# PCB_Keyboard_mark-2.net
KiCad netlist of a schematic drawn in EasyEDA
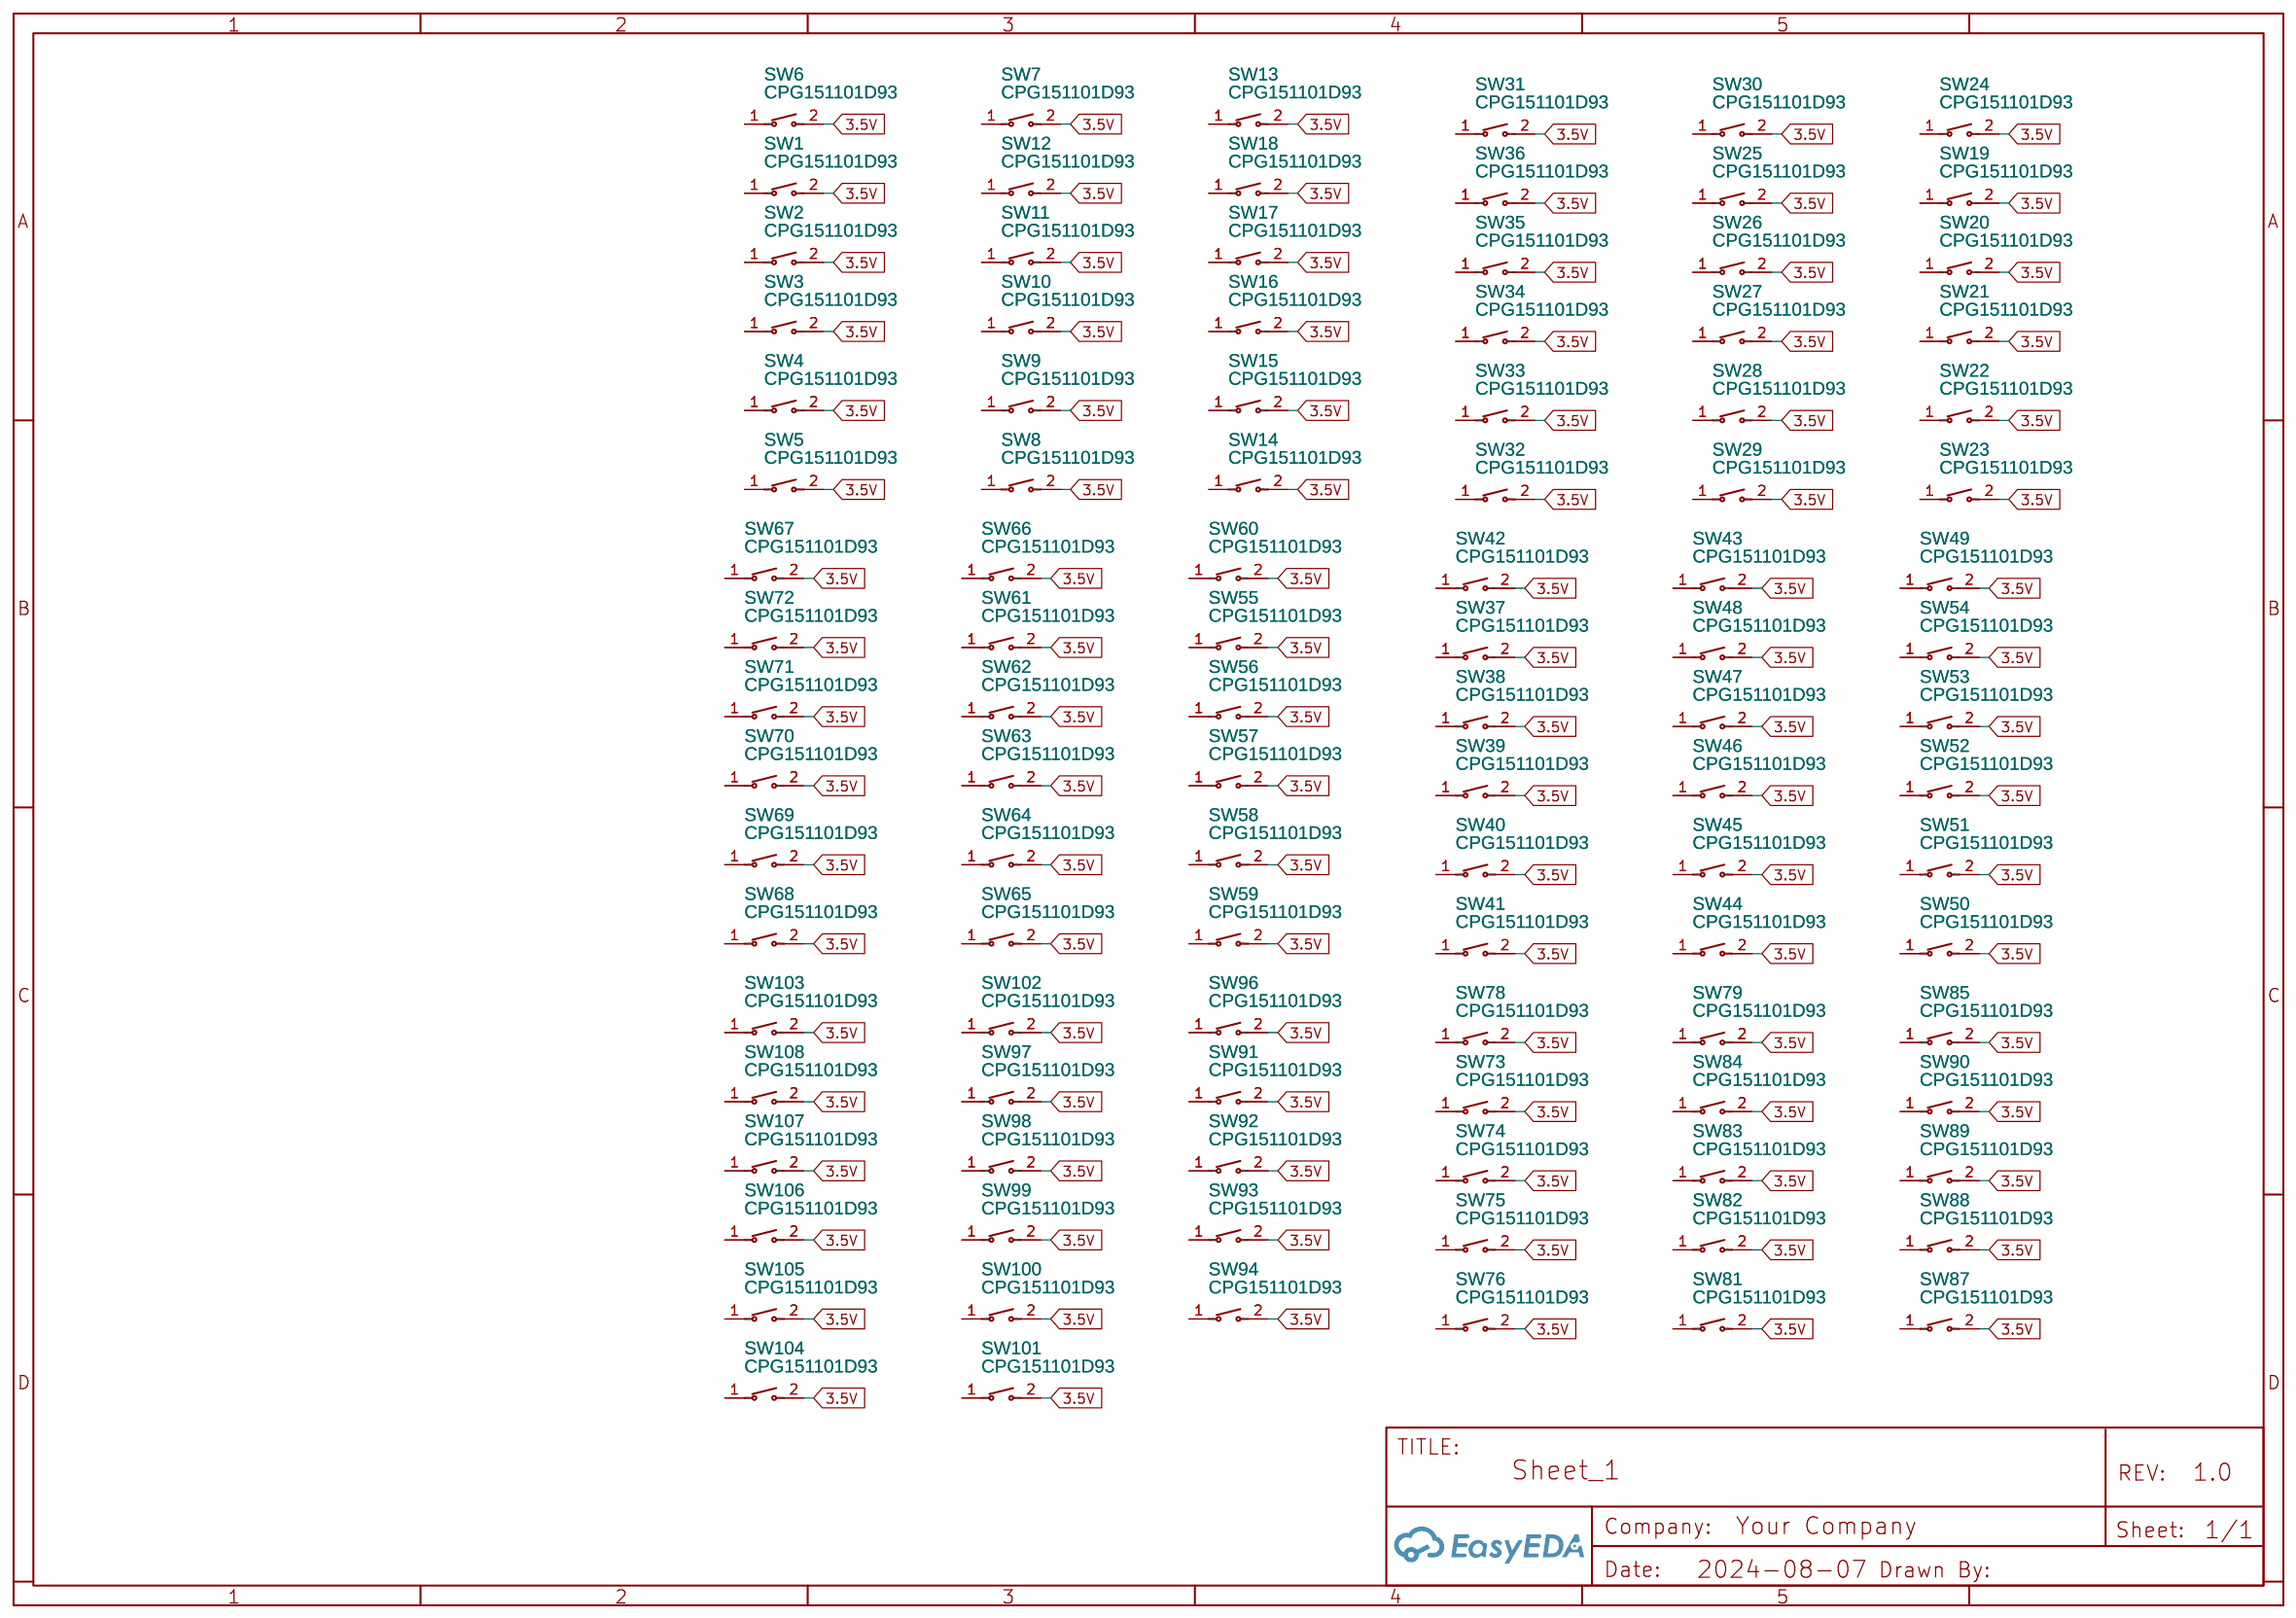
[diagram p0: schematic sheet]

(export (version "E")
  (design (tool "Eeschema 10.0.6"))
  (components
    (comp (ref "SW1")
      (value "CPG151101D93")
      (fields (field (name "Manufacturer") "Kailh(凯华)"))
      (libsource (lib "") (part "CPG151101D93"))
    )
    (comp (ref "SW2")
      (value "CPG151101D93")
      (fields (field (name "Manufacturer") "Kailh(凯华)"))
      (libsource (lib "") (part "CPG151101D93"))
    )
    (comp (ref "SW3")
      (value "CPG151101D93")
      (fields (field (name "Manufacturer") "Kailh(凯华)"))
      (libsource (lib "") (part "CPG151101D93"))
    )
    (comp (ref "SW4")
      (value "CPG151101D93")
      (fields (field (name "Manufacturer") "Kailh(凯华)"))
      (libsource (lib "") (part "CPG151101D93"))
    )
    (comp (ref "SW5")
      (value "CPG151101D93")
      (fields (field (name "Manufacturer") "Kailh(凯华)"))
      (libsource (lib "") (part "CPG151101D93"))
    )
    (comp (ref "SW6")
      (value "CPG151101D93")
      (fields (field (name "Manufacturer") "Kailh(凯华)"))
      (libsource (lib "") (part "CPG151101D93"))
    )
    (comp (ref "SW7")
      (value "CPG151101D93")
      (fields (field (name "Manufacturer") "Kailh(凯华)"))
      (libsource (lib "") (part "CPG151101D93"))
    )
    (comp (ref "SW8")
      (value "CPG151101D93")
      (fields (field (name "Manufacturer") "Kailh(凯华)"))
      (libsource (lib "") (part "CPG151101D93"))
    )
    (comp (ref "SW9")
      (value "CPG151101D93")
      (fields (field (name "Manufacturer") "Kailh(凯华)"))
      (libsource (lib "") (part "CPG151101D93"))
    )
    (comp (ref "SW10")
      (value "CPG151101D93")
      (fields (field (name "Manufacturer") "Kailh(凯华)"))
      (libsource (lib "") (part "CPG151101D93"))
    )
    (comp (ref "SW11")
      (value "CPG151101D93")
      (fields (field (name "Manufacturer") "Kailh(凯华)"))
      (libsource (lib "") (part "CPG151101D93"))
    )
    (comp (ref "SW12")
      (value "CPG151101D93")
      (fields (field (name "Manufacturer") "Kailh(凯华)"))
      (libsource (lib "") (part "CPG151101D93"))
    )
    (comp (ref "SW13")
      (value "CPG151101D93")
      (fields (field (name "Manufacturer") "Kailh(凯华)"))
      (libsource (lib "") (part "CPG151101D93"))
    )
    (comp (ref "SW14")
      (value "CPG151101D93")
      (fields (field (name "Manufacturer") "Kailh(凯华)"))
      (libsource (lib "") (part "CPG151101D93"))
    )
    (comp (ref "SW15")
      (value "CPG151101D93")
      (fields (field (name "Manufacturer") "Kailh(凯华)"))
      (libsource (lib "") (part "CPG151101D93"))
    )
    (comp (ref "SW16")
      (value "CPG151101D93")
      (fields (field (name "Manufacturer") "Kailh(凯华)"))
      (libsource (lib "") (part "CPG151101D93"))
    )
    (comp (ref "SW17")
      (value "CPG151101D93")
      (fields (field (name "Manufacturer") "Kailh(凯华)"))
      (libsource (lib "") (part "CPG151101D93"))
    )
    (comp (ref "SW18")
      (value "CPG151101D93")
      (fields (field (name "Manufacturer") "Kailh(凯华)"))
      (libsource (lib "") (part "CPG151101D93"))
    )
    (comp (ref "SW19")
      (value "CPG151101D93")
      (fields (field (name "Manufacturer") "Kailh(凯华)"))
      (libsource (lib "") (part "CPG151101D93"))
    )
    (comp (ref "SW20")
      (value "CPG151101D93")
      (fields (field (name "Manufacturer") "Kailh(凯华)"))
      (libsource (lib "") (part "CPG151101D93"))
    )
    (comp (ref "SW21")
      (value "CPG151101D93")
      (fields (field (name "Manufacturer") "Kailh(凯华)"))
      (libsource (lib "") (part "CPG151101D93"))
    )
    (comp (ref "SW22")
      (value "CPG151101D93")
      (fields (field (name "Manufacturer") "Kailh(凯华)"))
      (libsource (lib "") (part "CPG151101D93"))
    )
    (comp (ref "SW23")
      (value "CPG151101D93")
      (fields (field (name "Manufacturer") "Kailh(凯华)"))
      (libsource (lib "") (part "CPG151101D93"))
    )
    (comp (ref "SW24")
      (value "CPG151101D93")
      (fields (field (name "Manufacturer") "Kailh(凯华)"))
      (libsource (lib "") (part "CPG151101D93"))
    )
    (comp (ref "SW25")
      (value "CPG151101D93")
      (fields (field (name "Manufacturer") "Kailh(凯华)"))
      (libsource (lib "") (part "CPG151101D93"))
    )
    (comp (ref "SW26")
      (value "CPG151101D93")
      (fields (field (name "Manufacturer") "Kailh(凯华)"))
      (libsource (lib "") (part "CPG151101D93"))
    )
    (comp (ref "SW27")
      (value "CPG151101D93")
      (fields (field (name "Manufacturer") "Kailh(凯华)"))
      (libsource (lib "") (part "CPG151101D93"))
    )
    (comp (ref "SW28")
      (value "CPG151101D93")
      (fields (field (name "Manufacturer") "Kailh(凯华)"))
      (libsource (lib "") (part "CPG151101D93"))
    )
    (comp (ref "SW29")
      (value "CPG151101D93")
      (fields (field (name "Manufacturer") "Kailh(凯华)"))
      (libsource (lib "") (part "CPG151101D93"))
    )
    (comp (ref "SW30")
      (value "CPG151101D93")
      (fields (field (name "Manufacturer") "Kailh(凯华)"))
      (libsource (lib "") (part "CPG151101D93"))
    )
    (comp (ref "SW31")
      (value "CPG151101D93")
      (fields (field (name "Manufacturer") "Kailh(凯华)"))
      (libsource (lib "") (part "CPG151101D93"))
    )
    (comp (ref "SW32")
      (value "CPG151101D93")
      (fields (field (name "Manufacturer") "Kailh(凯华)"))
      (libsource (lib "") (part "CPG151101D93"))
    )
    (comp (ref "SW33")
      (value "CPG151101D93")
      (fields (field (name "Manufacturer") "Kailh(凯华)"))
      (libsource (lib "") (part "CPG151101D93"))
    )
    (comp (ref "SW34")
      (value "CPG151101D93")
      (fields (field (name "Manufacturer") "Kailh(凯华)"))
      (libsource (lib "") (part "CPG151101D93"))
    )
    (comp (ref "SW35")
      (value "CPG151101D93")
      (fields (field (name "Manufacturer") "Kailh(凯华)"))
      (libsource (lib "") (part "CPG151101D93"))
    )
    (comp (ref "SW36")
      (value "CPG151101D93")
      (fields (field (name "Manufacturer") "Kailh(凯华)"))
      (libsource (lib "") (part "CPG151101D93"))
    )
    (comp (ref "SW37")
      (value "CPG151101D93")
      (fields (field (name "Manufacturer") "Kailh(凯华)"))
      (libsource (lib "") (part "CPG151101D93"))
    )
    (comp (ref "SW38")
      (value "CPG151101D93")
      (fields (field (name "Manufacturer") "Kailh(凯华)"))
      (libsource (lib "") (part "CPG151101D93"))
    )
    (comp (ref "SW39")
      (value "CPG151101D93")
      (fields (field (name "Manufacturer") "Kailh(凯华)"))
      (libsource (lib "") (part "CPG151101D93"))
    )
    (comp (ref "SW40")
      (value "CPG151101D93")
      (fields (field (name "Manufacturer") "Kailh(凯华)"))
      (libsource (lib "") (part "CPG151101D93"))
    )
    (comp (ref "SW41")
      (value "CPG151101D93")
      (fields (field (name "Manufacturer") "Kailh(凯华)"))
      (libsource (lib "") (part "CPG151101D93"))
    )
    (comp (ref "SW42")
      (value "CPG151101D93")
      (fields (field (name "Manufacturer") "Kailh(凯华)"))
      (libsource (lib "") (part "CPG151101D93"))
    )
    (comp (ref "SW43")
      (value "CPG151101D93")
      (fields (field (name "Manufacturer") "Kailh(凯华)"))
      (libsource (lib "") (part "CPG151101D93"))
    )
    (comp (ref "SW44")
      (value "CPG151101D93")
      (fields (field (name "Manufacturer") "Kailh(凯华)"))
      (libsource (lib "") (part "CPG151101D93"))
    )
    (comp (ref "SW45")
      (value "CPG151101D93")
      (fields (field (name "Manufacturer") "Kailh(凯华)"))
      (libsource (lib "") (part "CPG151101D93"))
    )
    (comp (ref "SW46")
      (value "CPG151101D93")
      (fields (field (name "Manufacturer") "Kailh(凯华)"))
      (libsource (lib "") (part "CPG151101D93"))
    )
    (comp (ref "SW47")
      (value "CPG151101D93")
      (fields (field (name "Manufacturer") "Kailh(凯华)"))
      (libsource (lib "") (part "CPG151101D93"))
    )
    (comp (ref "SW48")
      (value "CPG151101D93")
      (fields (field (name "Manufacturer") "Kailh(凯华)"))
      (libsource (lib "") (part "CPG151101D93"))
    )
    (comp (ref "SW49")
      (value "CPG151101D93")
      (fields (field (name "Manufacturer") "Kailh(凯华)"))
      (libsource (lib "") (part "CPG151101D93"))
    )
    (comp (ref "SW50")
      (value "CPG151101D93")
      (fields (field (name "Manufacturer") "Kailh(凯华)"))
      (libsource (lib "") (part "CPG151101D93"))
    )
    (comp (ref "SW51")
      (value "CPG151101D93")
      (fields (field (name "Manufacturer") "Kailh(凯华)"))
      (libsource (lib "") (part "CPG151101D93"))
    )
    (comp (ref "SW52")
      (value "CPG151101D93")
      (fields (field (name "Manufacturer") "Kailh(凯华)"))
      (libsource (lib "") (part "CPG151101D93"))
    )
    (comp (ref "SW53")
      (value "CPG151101D93")
      (fields (field (name "Manufacturer") "Kailh(凯华)"))
      (libsource (lib "") (part "CPG151101D93"))
    )
    (comp (ref "SW54")
      (value "CPG151101D93")
      (fields (field (name "Manufacturer") "Kailh(凯华)"))
      (libsource (lib "") (part "CPG151101D93"))
    )
    (comp (ref "SW55")
      (value "CPG151101D93")
      (fields (field (name "Manufacturer") "Kailh(凯华)"))
      (libsource (lib "") (part "CPG151101D93"))
    )
    (comp (ref "SW56")
      (value "CPG151101D93")
      (fields (field (name "Manufacturer") "Kailh(凯华)"))
      (libsource (lib "") (part "CPG151101D93"))
    )
    (comp (ref "SW57")
      (value "CPG151101D93")
      (fields (field (name "Manufacturer") "Kailh(凯华)"))
      (libsource (lib "") (part "CPG151101D93"))
    )
    (comp (ref "SW58")
      (value "CPG151101D93")
      (fields (field (name "Manufacturer") "Kailh(凯华)"))
      (libsource (lib "") (part "CPG151101D93"))
    )
    (comp (ref "SW59")
      (value "CPG151101D93")
      (fields (field (name "Manufacturer") "Kailh(凯华)"))
      (libsource (lib "") (part "CPG151101D93"))
    )
    (comp (ref "SW60")
      (value "CPG151101D93")
      (fields (field (name "Manufacturer") "Kailh(凯华)"))
      (libsource (lib "") (part "CPG151101D93"))
    )
    (comp (ref "SW61")
      (value "CPG151101D93")
      (fields (field (name "Manufacturer") "Kailh(凯华)"))
      (libsource (lib "") (part "CPG151101D93"))
    )
    (comp (ref "SW62")
      (value "CPG151101D93")
      (fields (field (name "Manufacturer") "Kailh(凯华)"))
      (libsource (lib "") (part "CPG151101D93"))
    )
    (comp (ref "SW63")
      (value "CPG151101D93")
      (fields (field (name "Manufacturer") "Kailh(凯华)"))
      (libsource (lib "") (part "CPG151101D93"))
    )
    (comp (ref "SW64")
      (value "CPG151101D93")
      (fields (field (name "Manufacturer") "Kailh(凯华)"))
      (libsource (lib "") (part "CPG151101D93"))
    )
    (comp (ref "SW65")
      (value "CPG151101D93")
      (fields (field (name "Manufacturer") "Kailh(凯华)"))
      (libsource (lib "") (part "CPG151101D93"))
    )
    (comp (ref "SW66")
      (value "CPG151101D93")
      (fields (field (name "Manufacturer") "Kailh(凯华)"))
      (libsource (lib "") (part "CPG151101D93"))
    )
    (comp (ref "SW67")
      (value "CPG151101D93")
      (fields (field (name "Manufacturer") "Kailh(凯华)"))
      (libsource (lib "") (part "CPG151101D93"))
    )
    (comp (ref "SW68")
      (value "CPG151101D93")
      (fields (field (name "Manufacturer") "Kailh(凯华)"))
      (libsource (lib "") (part "CPG151101D93"))
    )
    (comp (ref "SW69")
      (value "CPG151101D93")
      (fields (field (name "Manufacturer") "Kailh(凯华)"))
      (libsource (lib "") (part "CPG151101D93"))
    )
    (comp (ref "SW70")
      (value "CPG151101D93")
      (fields (field (name "Manufacturer") "Kailh(凯华)"))
      (libsource (lib "") (part "CPG151101D93"))
    )
    (comp (ref "SW71")
      (value "CPG151101D93")
      (fields (field (name "Manufacturer") "Kailh(凯华)"))
      (libsource (lib "") (part "CPG151101D93"))
    )
    (comp (ref "SW72")
      (value "CPG151101D93")
      (fields (field (name "Manufacturer") "Kailh(凯华)"))
      (libsource (lib "") (part "CPG151101D93"))
    )
    (comp (ref "SW73")
      (value "CPG151101D93")
      (fields (field (name "Manufacturer") "Kailh(凯华)"))
      (libsource (lib "") (part "CPG151101D93"))
    )
    (comp (ref "SW74")
      (value "CPG151101D93")
      (fields (field (name "Manufacturer") "Kailh(凯华)"))
      (libsource (lib "") (part "CPG151101D93"))
    )
    (comp (ref "SW75")
      (value "CPG151101D93")
      (fields (field (name "Manufacturer") "Kailh(凯华)"))
      (libsource (lib "") (part "CPG151101D93"))
    )
    (comp (ref "SW76")
      (value "CPG151101D93")
      (fields (field (name "Manufacturer") "Kailh(凯华)"))
      (libsource (lib "") (part "CPG151101D93"))
    )
    (comp (ref "SW78")
      (value "CPG151101D93")
      (fields (field (name "Manufacturer") "Kailh(凯华)"))
      (libsource (lib "") (part "CPG151101D93"))
    )
    (comp (ref "SW79")
      (value "CPG151101D93")
      (fields (field (name "Manufacturer") "Kailh(凯华)"))
      (libsource (lib "") (part "CPG151101D93"))
    )
    (comp (ref "SW81")
      (value "CPG151101D93")
      (fields (field (name "Manufacturer") "Kailh(凯华)"))
      (libsource (lib "") (part "CPG151101D93"))
    )
    (comp (ref "SW82")
      (value "CPG151101D93")
      (fields (field (name "Manufacturer") "Kailh(凯华)"))
      (libsource (lib "") (part "CPG151101D93"))
    )
    (comp (ref "SW83")
      (value "CPG151101D93")
      (fields (field (name "Manufacturer") "Kailh(凯华)"))
      (libsource (lib "") (part "CPG151101D93"))
    )
    (comp (ref "SW84")
      (value "CPG151101D93")
      (fields (field (name "Manufacturer") "Kailh(凯华)"))
      (libsource (lib "") (part "CPG151101D93"))
    )
    (comp (ref "SW85")
      (value "CPG151101D93")
      (fields (field (name "Manufacturer") "Kailh(凯华)"))
      (libsource (lib "") (part "CPG151101D93"))
    )
    (comp (ref "SW87")
      (value "CPG151101D93")
      (fields (field (name "Manufacturer") "Kailh(凯华)"))
      (libsource (lib "") (part "CPG151101D93"))
    )
    (comp (ref "SW88")
      (value "CPG151101D93")
      (fields (field (name "Manufacturer") "Kailh(凯华)"))
      (libsource (lib "") (part "CPG151101D93"))
    )
    (comp (ref "SW89")
      (value "CPG151101D93")
      (fields (field (name "Manufacturer") "Kailh(凯华)"))
      (libsource (lib "") (part "CPG151101D93"))
    )
    (comp (ref "SW90")
      (value "CPG151101D93")
      (fields (field (name "Manufacturer") "Kailh(凯华)"))
      (libsource (lib "") (part "CPG151101D93"))
    )
    (comp (ref "SW91")
      (value "CPG151101D93")
      (fields (field (name "Manufacturer") "Kailh(凯华)"))
      (libsource (lib "") (part "CPG151101D93"))
    )
    (comp (ref "SW92")
      (value "CPG151101D93")
      (fields (field (name "Manufacturer") "Kailh(凯华)"))
      (libsource (lib "") (part "CPG151101D93"))
    )
    (comp (ref "SW93")
      (value "CPG151101D93")
      (fields (field (name "Manufacturer") "Kailh(凯华)"))
      (libsource (lib "") (part "CPG151101D93"))
    )
    (comp (ref "SW94")
      (value "CPG151101D93")
      (fields (field (name "Manufacturer") "Kailh(凯华)"))
      (libsource (lib "") (part "CPG151101D93"))
    )
    (comp (ref "SW96")
      (value "CPG151101D93")
      (fields (field (name "Manufacturer") "Kailh(凯华)"))
      (libsource (lib "") (part "CPG151101D93"))
    )
    (comp (ref "SW97")
      (value "CPG151101D93")
      (fields (field (name "Manufacturer") "Kailh(凯华)"))
      (libsource (lib "") (part "CPG151101D93"))
    )
    (comp (ref "SW98")
      (value "CPG151101D93")
      (fields (field (name "Manufacturer") "Kailh(凯华)"))
      (libsource (lib "") (part "CPG151101D93"))
    )
    (comp (ref "SW99")
      (value "CPG151101D93")
      (fields (field (name "Manufacturer") "Kailh(凯华)"))
      (libsource (lib "") (part "CPG151101D93"))
    )
    (comp (ref "SW100")
      (value "CPG151101D93")
      (fields (field (name "Manufacturer") "Kailh(凯华)"))
      (libsource (lib "") (part "CPG151101D93"))
    )
    (comp (ref "SW101")
      (value "CPG151101D93")
      (fields (field (name "Manufacturer") "Kailh(凯华)"))
      (libsource (lib "") (part "CPG151101D93"))
    )
    (comp (ref "SW102")
      (value "CPG151101D93")
      (fields (field (name "Manufacturer") "Kailh(凯华)"))
      (libsource (lib "") (part "CPG151101D93"))
    )
    (comp (ref "SW103")
      (value "CPG151101D93")
      (fields (field (name "Manufacturer") "Kailh(凯华)"))
      (libsource (lib "") (part "CPG151101D93"))
    )
    (comp (ref "SW104")
      (value "CPG151101D93")
      (fields (field (name "Manufacturer") "Kailh(凯华)"))
      (libsource (lib "") (part "CPG151101D93"))
    )
    (comp (ref "SW105")
      (value "CPG151101D93")
      (fields (field (name "Manufacturer") "Kailh(凯华)"))
      (libsource (lib "") (part "CPG151101D93"))
    )
    (comp (ref "SW106")
      (value "CPG151101D93")
      (fields (field (name "Manufacturer") "Kailh(凯华)"))
      (libsource (lib "") (part "CPG151101D93"))
    )
    (comp (ref "SW107")
      (value "CPG151101D93")
      (fields (field (name "Manufacturer") "Kailh(凯华)"))
      (libsource (lib "") (part "CPG151101D93"))
    )
    (comp (ref "SW108")
      (value "CPG151101D93")
      (fields (field (name "Manufacturer") "Kailh(凯华)"))
      (libsource (lib "") (part "CPG151101D93"))
    )
  )
  (nets
    (net (code "1") (name "3.5V") (class "Default")
      (node (ref "SW1") (pin "2") (pinfunction "2_2") (pintype "unspecified"))
      (node (ref "SW10") (pin "2") (pinfunction "2_2") (pintype "unspecified"))
      (node (ref "SW100") (pin "2") (pinfunction "2_2") (pintype "unspecified"))
      (node (ref "SW101") (pin "2") (pinfunction "2_2") (pintype "unspecified"))
      (node (ref "SW102") (pin "2") (pinfunction "2_2") (pintype "unspecified"))
      (node (ref "SW103") (pin "2") (pinfunction "2_2") (pintype "unspecified"))
      (node (ref "SW104") (pin "2") (pinfunction "2_2") (pintype "unspecified"))
      (node (ref "SW105") (pin "2") (pinfunction "2_2") (pintype "unspecified"))
      (node (ref "SW106") (pin "2") (pinfunction "2_2") (pintype "unspecified"))
      (node (ref "SW107") (pin "2") (pinfunction "2_2") (pintype "unspecified"))
      (node (ref "SW108") (pin "2") (pinfunction "2_2") (pintype "unspecified"))
      (node (ref "SW11") (pin "2") (pinfunction "2_2") (pintype "unspecified"))
      (node (ref "SW12") (pin "2") (pinfunction "2_2") (pintype "unspecified"))
      (node (ref "SW13") (pin "2") (pinfunction "2_2") (pintype "unspecified"))
      (node (ref "SW14") (pin "2") (pinfunction "2_2") (pintype "unspecified"))
      (node (ref "SW15") (pin "2") (pinfunction "2_2") (pintype "unspecified"))
      (node (ref "SW16") (pin "2") (pinfunction "2_2") (pintype "unspecified"))
      (node (ref "SW17") (pin "2") (pinfunction "2_2") (pintype "unspecified"))
      (node (ref "SW18") (pin "2") (pinfunction "2_2") (pintype "unspecified"))
      (node (ref "SW19") (pin "2") (pinfunction "2_2") (pintype "unspecified"))
      (node (ref "SW2") (pin "2") (pinfunction "2_2") (pintype "unspecified"))
      (node (ref "SW20") (pin "2") (pinfunction "2_2") (pintype "unspecified"))
      (node (ref "SW21") (pin "2") (pinfunction "2_2") (pintype "unspecified"))
      (node (ref "SW22") (pin "2") (pinfunction "2_2") (pintype "unspecified"))
      (node (ref "SW23") (pin "2") (pinfunction "2_2") (pintype "unspecified"))
      (node (ref "SW24") (pin "2") (pinfunction "2_2") (pintype "unspecified"))
      (node (ref "SW25") (pin "2") (pinfunction "2_2") (pintype "unspecified"))
      (node (ref "SW26") (pin "2") (pinfunction "2_2") (pintype "unspecified"))
      (node (ref "SW27") (pin "2") (pinfunction "2_2") (pintype "unspecified"))
      (node (ref "SW28") (pin "2") (pinfunction "2_2") (pintype "unspecified"))
      (node (ref "SW29") (pin "2") (pinfunction "2_2") (pintype "unspecified"))
      (node (ref "SW3") (pin "2") (pinfunction "2_2") (pintype "unspecified"))
      (node (ref "SW30") (pin "2") (pinfunction "2_2") (pintype "unspecified"))
      (node (ref "SW31") (pin "2") (pinfunction "2_2") (pintype "unspecified"))
      (node (ref "SW32") (pin "2") (pinfunction "2_2") (pintype "unspecified"))
      (node (ref "SW33") (pin "2") (pinfunction "2_2") (pintype "unspecified"))
      (node (ref "SW34") (pin "2") (pinfunction "2_2") (pintype "unspecified"))
      (node (ref "SW35") (pin "2") (pinfunction "2_2") (pintype "unspecified"))
      (node (ref "SW36") (pin "2") (pinfunction "2_2") (pintype "unspecified"))
      (node (ref "SW37") (pin "2") (pinfunction "2_2") (pintype "unspecified"))
      (node (ref "SW38") (pin "2") (pinfunction "2_2") (pintype "unspecified"))
      (node (ref "SW39") (pin "2") (pinfunction "2_2") (pintype "unspecified"))
      (node (ref "SW4") (pin "2") (pinfunction "2_2") (pintype "unspecified"))
      (node (ref "SW40") (pin "2") (pinfunction "2_2") (pintype "unspecified"))
      (node (ref "SW41") (pin "2") (pinfunction "2_2") (pintype "unspecified"))
      (node (ref "SW42") (pin "2") (pinfunction "2_2") (pintype "unspecified"))
      (node (ref "SW43") (pin "2") (pinfunction "2_2") (pintype "unspecified"))
      (node (ref "SW44") (pin "2") (pinfunction "2_2") (pintype "unspecified"))
      (node (ref "SW45") (pin "2") (pinfunction "2_2") (pintype "unspecified"))
      (node (ref "SW46") (pin "2") (pinfunction "2_2") (pintype "unspecified"))
      (node (ref "SW47") (pin "2") (pinfunction "2_2") (pintype "unspecified"))
      (node (ref "SW48") (pin "2") (pinfunction "2_2") (pintype "unspecified"))
      (node (ref "SW49") (pin "2") (pinfunction "2_2") (pintype "unspecified"))
      (node (ref "SW5") (pin "2") (pinfunction "2_2") (pintype "unspecified"))
      (node (ref "SW50") (pin "2") (pinfunction "2_2") (pintype "unspecified"))
      (node (ref "SW51") (pin "2") (pinfunction "2_2") (pintype "unspecified"))
      (node (ref "SW52") (pin "2") (pinfunction "2_2") (pintype "unspecified"))
      (node (ref "SW53") (pin "2") (pinfunction "2_2") (pintype "unspecified"))
      (node (ref "SW54") (pin "2") (pinfunction "2_2") (pintype "unspecified"))
      (node (ref "SW55") (pin "2") (pinfunction "2_2") (pintype "unspecified"))
      (node (ref "SW56") (pin "2") (pinfunction "2_2") (pintype "unspecified"))
      (node (ref "SW57") (pin "2") (pinfunction "2_2") (pintype "unspecified"))
      (node (ref "SW58") (pin "2") (pinfunction "2_2") (pintype "unspecified"))
      (node (ref "SW59") (pin "2") (pinfunction "2_2") (pintype "unspecified"))
      (node (ref "SW6") (pin "2") (pinfunction "2_2") (pintype "unspecified"))
      (node (ref "SW60") (pin "2") (pinfunction "2_2") (pintype "unspecified"))
      (node (ref "SW61") (pin "2") (pinfunction "2_2") (pintype "unspecified"))
      (node (ref "SW62") (pin "2") (pinfunction "2_2") (pintype "unspecified"))
      (node (ref "SW63") (pin "2") (pinfunction "2_2") (pintype "unspecified"))
      (node (ref "SW64") (pin "2") (pinfunction "2_2") (pintype "unspecified"))
      (node (ref "SW65") (pin "2") (pinfunction "2_2") (pintype "unspecified"))
      (node (ref "SW66") (pin "2") (pinfunction "2_2") (pintype "unspecified"))
      (node (ref "SW67") (pin "2") (pinfunction "2_2") (pintype "unspecified"))
      (node (ref "SW68") (pin "2") (pinfunction "2_2") (pintype "unspecified"))
      (node (ref "SW69") (pin "2") (pinfunction "2_2") (pintype "unspecified"))
      (node (ref "SW7") (pin "2") (pinfunction "2_2") (pintype "unspecified"))
      (node (ref "SW70") (pin "2") (pinfunction "2_2") (pintype "unspecified"))
      (node (ref "SW71") (pin "2") (pinfunction "2_2") (pintype "unspecified"))
      (node (ref "SW72") (pin "2") (pinfunction "2_2") (pintype "unspecified"))
      (node (ref "SW73") (pin "2") (pinfunction "2_2") (pintype "unspecified"))
      (node (ref "SW74") (pin "2") (pinfunction "2_2") (pintype "unspecified"))
      (node (ref "SW75") (pin "2") (pinfunction "2_2") (pintype "unspecified"))
      (node (ref "SW76") (pin "2") (pinfunction "2_2") (pintype "unspecified"))
      (node (ref "SW78") (pin "2") (pinfunction "2_2") (pintype "unspecified"))
      (node (ref "SW79") (pin "2") (pinfunction "2_2") (pintype "unspecified"))
      (node (ref "SW8") (pin "2") (pinfunction "2_2") (pintype "unspecified"))
      (node (ref "SW81") (pin "2") (pinfunction "2_2") (pintype "unspecified"))
      (node (ref "SW82") (pin "2") (pinfunction "2_2") (pintype "unspecified"))
      (node (ref "SW83") (pin "2") (pinfunction "2_2") (pintype "unspecified"))
      (node (ref "SW84") (pin "2") (pinfunction "2_2") (pintype "unspecified"))
      (node (ref "SW85") (pin "2") (pinfunction "2_2") (pintype "unspecified"))
      (node (ref "SW87") (pin "2") (pinfunction "2_2") (pintype "unspecified"))
      (node (ref "SW88") (pin "2") (pinfunction "2_2") (pintype "unspecified"))
      (node (ref "SW89") (pin "2") (pinfunction "2_2") (pintype "unspecified"))
      (node (ref "SW9") (pin "2") (pinfunction "2_2") (pintype "unspecified"))
      (node (ref "SW90") (pin "2") (pinfunction "2_2") (pintype "unspecified"))
      (node (ref "SW91") (pin "2") (pinfunction "2_2") (pintype "unspecified"))
      (node (ref "SW92") (pin "2") (pinfunction "2_2") (pintype "unspecified"))
      (node (ref "SW93") (pin "2") (pinfunction "2_2") (pintype "unspecified"))
      (node (ref "SW94") (pin "2") (pinfunction "2_2") (pintype "unspecified"))
      (node (ref "SW96") (pin "2") (pinfunction "2_2") (pintype "unspecified"))
      (node (ref "SW97") (pin "2") (pinfunction "2_2") (pintype "unspecified"))
      (node (ref "SW98") (pin "2") (pinfunction "2_2") (pintype "unspecified"))
      (node (ref "SW99") (pin "2") (pinfunction "2_2") (pintype "unspecified"))
    )
    (net (code "2") (name "unconnected-(SW1-Pad1)") (class "Default")
      (node (ref "SW1") (pin "1") (pinfunction "1_1") (pintype "unspecified"))
    )
    (net (code "3") (name "unconnected-(SW2-Pad1)") (class "Default")
      (node (ref "SW2") (pin "1") (pinfunction "1_1") (pintype "unspecified"))
    )
    (net (code "4") (name "unconnected-(SW3-Pad1)") (class "Default")
      (node (ref "SW3") (pin "1") (pinfunction "1_1") (pintype "unspecified"))
    )
    (net (code "5") (name "unconnected-(SW4-Pad1)") (class "Default")
      (node (ref "SW4") (pin "1") (pinfunction "1_1") (pintype "unspecified"))
    )
    (net (code "6") (name "unconnected-(SW5-Pad1)") (class "Default")
      (node (ref "SW5") (pin "1") (pinfunction "1_1") (pintype "unspecified"))
    )
    (net (code "7") (name "unconnected-(SW6-Pad1)") (class "Default")
      (node (ref "SW6") (pin "1") (pinfunction "1_1") (pintype "unspecified"))
    )
    (net (code "8") (name "unconnected-(SW7-Pad1)") (class "Default")
      (node (ref "SW7") (pin "1") (pinfunction "1_1") (pintype "unspecified"))
    )
    (net (code "9") (name "unconnected-(SW8-Pad1)") (class "Default")
      (node (ref "SW8") (pin "1") (pinfunction "1_1") (pintype "unspecified"))
    )
    (net (code "10") (name "unconnected-(SW9-Pad1)") (class "Default")
      (node (ref "SW9") (pin "1") (pinfunction "1_1") (pintype "unspecified"))
    )
    (net (code "11") (name "unconnected-(SW10-Pad1)") (class "Default")
      (node (ref "SW10") (pin "1") (pinfunction "1_1") (pintype "unspecified"))
    )
    (net (code "12") (name "unconnected-(SW11-Pad1)") (class "Default")
      (node (ref "SW11") (pin "1") (pinfunction "1_1") (pintype "unspecified"))
    )
    (net (code "13") (name "unconnected-(SW12-Pad1)") (class "Default")
      (node (ref "SW12") (pin "1") (pinfunction "1_1") (pintype "unspecified"))
    )
    (net (code "14") (name "unconnected-(SW13-Pad1)") (class "Default")
      (node (ref "SW13") (pin "1") (pinfunction "1_1") (pintype "unspecified"))
    )
    (net (code "15") (name "unconnected-(SW14-Pad1)") (class "Default")
      (node (ref "SW14") (pin "1") (pinfunction "1_1") (pintype "unspecified"))
    )
    (net (code "16") (name "unconnected-(SW15-Pad1)") (class "Default")
      (node (ref "SW15") (pin "1") (pinfunction "1_1") (pintype "unspecified"))
    )
    (net (code "17") (name "unconnected-(SW16-Pad1)") (class "Default")
      (node (ref "SW16") (pin "1") (pinfunction "1_1") (pintype "unspecified"))
    )
    (net (code "18") (name "unconnected-(SW17-Pad1)") (class "Default")
      (node (ref "SW17") (pin "1") (pinfunction "1_1") (pintype "unspecified"))
    )
    (net (code "19") (name "unconnected-(SW18-Pad1)") (class "Default")
      (node (ref "SW18") (pin "1") (pinfunction "1_1") (pintype "unspecified"))
    )
    (net (code "20") (name "unconnected-(SW19-Pad1)") (class "Default")
      (node (ref "SW19") (pin "1") (pinfunction "1_1") (pintype "unspecified"))
    )
    (net (code "21") (name "unconnected-(SW20-Pad1)") (class "Default")
      (node (ref "SW20") (pin "1") (pinfunction "1_1") (pintype "unspecified"))
    )
    (net (code "22") (name "unconnected-(SW21-Pad1)") (class "Default")
      (node (ref "SW21") (pin "1") (pinfunction "1_1") (pintype "unspecified"))
    )
    (net (code "23") (name "unconnected-(SW22-Pad1)") (class "Default")
      (node (ref "SW22") (pin "1") (pinfunction "1_1") (pintype "unspecified"))
    )
    (net (code "24") (name "unconnected-(SW23-Pad1)") (class "Default")
      (node (ref "SW23") (pin "1") (pinfunction "1_1") (pintype "unspecified"))
    )
    (net (code "25") (name "unconnected-(SW24-Pad1)") (class "Default")
      (node (ref "SW24") (pin "1") (pinfunction "1_1") (pintype "unspecified"))
    )
    (net (code "26") (name "unconnected-(SW25-Pad1)") (class "Default")
      (node (ref "SW25") (pin "1") (pinfunction "1_1") (pintype "unspecified"))
    )
    (net (code "27") (name "unconnected-(SW26-Pad1)") (class "Default")
      (node (ref "SW26") (pin "1") (pinfunction "1_1") (pintype "unspecified"))
    )
    (net (code "28") (name "unconnected-(SW27-Pad1)") (class "Default")
      (node (ref "SW27") (pin "1") (pinfunction "1_1") (pintype "unspecified"))
    )
    (net (code "29") (name "unconnected-(SW28-Pad1)") (class "Default")
      (node (ref "SW28") (pin "1") (pinfunction "1_1") (pintype "unspecified"))
    )
    (net (code "30") (name "unconnected-(SW29-Pad1)") (class "Default")
      (node (ref "SW29") (pin "1") (pinfunction "1_1") (pintype "unspecified"))
    )
    (net (code "31") (name "unconnected-(SW30-Pad1)") (class "Default")
      (node (ref "SW30") (pin "1") (pinfunction "1_1") (pintype "unspecified"))
    )
    (net (code "32") (name "unconnected-(SW31-Pad1)") (class "Default")
      (node (ref "SW31") (pin "1") (pinfunction "1_1") (pintype "unspecified"))
    )
    (net (code "33") (name "unconnected-(SW32-Pad1)") (class "Default")
      (node (ref "SW32") (pin "1") (pinfunction "1_1") (pintype "unspecified"))
    )
    (net (code "34") (name "unconnected-(SW33-Pad1)") (class "Default")
      (node (ref "SW33") (pin "1") (pinfunction "1_1") (pintype "unspecified"))
    )
    (net (code "35") (name "unconnected-(SW34-Pad1)") (class "Default")
      (node (ref "SW34") (pin "1") (pinfunction "1_1") (pintype "unspecified"))
    )
    (net (code "36") (name "unconnected-(SW35-Pad1)") (class "Default")
      (node (ref "SW35") (pin "1") (pinfunction "1_1") (pintype "unspecified"))
    )
    (net (code "37") (name "unconnected-(SW36-Pad1)") (class "Default")
      (node (ref "SW36") (pin "1") (pinfunction "1_1") (pintype "unspecified"))
    )
    (net (code "38") (name "unconnected-(SW37-Pad1)") (class "Default")
      (node (ref "SW37") (pin "1") (pinfunction "1_1") (pintype "unspecified"))
    )
    (net (code "39") (name "unconnected-(SW38-Pad1)") (class "Default")
      (node (ref "SW38") (pin "1") (pinfunction "1_1") (pintype "unspecified"))
    )
    (net (code "40") (name "unconnected-(SW39-Pad1)") (class "Default")
      (node (ref "SW39") (pin "1") (pinfunction "1_1") (pintype "unspecified"))
    )
    (net (code "41") (name "unconnected-(SW40-Pad1)") (class "Default")
      (node (ref "SW40") (pin "1") (pinfunction "1_1") (pintype "unspecified"))
    )
    (net (code "42") (name "unconnected-(SW41-Pad1)") (class "Default")
      (node (ref "SW41") (pin "1") (pinfunction "1_1") (pintype "unspecified"))
    )
    (net (code "43") (name "unconnected-(SW42-Pad1)") (class "Default")
      (node (ref "SW42") (pin "1") (pinfunction "1_1") (pintype "unspecified"))
    )
    (net (code "44") (name "unconnected-(SW43-Pad1)") (class "Default")
      (node (ref "SW43") (pin "1") (pinfunction "1_1") (pintype "unspecified"))
    )
    (net (code "45") (name "unconnected-(SW44-Pad1)") (class "Default")
      (node (ref "SW44") (pin "1") (pinfunction "1_1") (pintype "unspecified"))
    )
    (net (code "46") (name "unconnected-(SW45-Pad1)") (class "Default")
      (node (ref "SW45") (pin "1") (pinfunction "1_1") (pintype "unspecified"))
    )
    (net (code "47") (name "unconnected-(SW46-Pad1)") (class "Default")
      (node (ref "SW46") (pin "1") (pinfunction "1_1") (pintype "unspecified"))
    )
    (net (code "48") (name "unconnected-(SW47-Pad1)") (class "Default")
      (node (ref "SW47") (pin "1") (pinfunction "1_1") (pintype "unspecified"))
    )
    (net (code "49") (name "unconnected-(SW48-Pad1)") (class "Default")
      (node (ref "SW48") (pin "1") (pinfunction "1_1") (pintype "unspecified"))
    )
    (net (code "50") (name "unconnected-(SW49-Pad1)") (class "Default")
      (node (ref "SW49") (pin "1") (pinfunction "1_1") (pintype "unspecified"))
    )
    (net (code "51") (name "unconnected-(SW50-Pad1)") (class "Default")
      (node (ref "SW50") (pin "1") (pinfunction "1_1") (pintype "unspecified"))
    )
    (net (code "52") (name "unconnected-(SW51-Pad1)") (class "Default")
      (node (ref "SW51") (pin "1") (pinfunction "1_1") (pintype "unspecified"))
    )
    (net (code "53") (name "unconnected-(SW52-Pad1)") (class "Default")
      (node (ref "SW52") (pin "1") (pinfunction "1_1") (pintype "unspecified"))
    )
    (net (code "54") (name "unconnected-(SW53-Pad1)") (class "Default")
      (node (ref "SW53") (pin "1") (pinfunction "1_1") (pintype "unspecified"))
    )
    (net (code "55") (name "unconnected-(SW54-Pad1)") (class "Default")
      (node (ref "SW54") (pin "1") (pinfunction "1_1") (pintype "unspecified"))
    )
    (net (code "56") (name "unconnected-(SW55-Pad1)") (class "Default")
      (node (ref "SW55") (pin "1") (pinfunction "1_1") (pintype "unspecified"))
    )
    (net (code "57") (name "unconnected-(SW56-Pad1)") (class "Default")
      (node (ref "SW56") (pin "1") (pinfunction "1_1") (pintype "unspecified"))
    )
    (net (code "58") (name "unconnected-(SW57-Pad1)") (class "Default")
      (node (ref "SW57") (pin "1") (pinfunction "1_1") (pintype "unspecified"))
    )
    (net (code "59") (name "unconnected-(SW58-Pad1)") (class "Default")
      (node (ref "SW58") (pin "1") (pinfunction "1_1") (pintype "unspecified"))
    )
    (net (code "60") (name "unconnected-(SW59-Pad1)") (class "Default")
      (node (ref "SW59") (pin "1") (pinfunction "1_1") (pintype "unspecified"))
    )
    (net (code "61") (name "unconnected-(SW60-Pad1)") (class "Default")
      (node (ref "SW60") (pin "1") (pinfunction "1_1") (pintype "unspecified"))
    )
    (net (code "62") (name "unconnected-(SW61-Pad1)") (class "Default")
      (node (ref "SW61") (pin "1") (pinfunction "1_1") (pintype "unspecified"))
    )
    (net (code "63") (name "unconnected-(SW62-Pad1)") (class "Default")
      (node (ref "SW62") (pin "1") (pinfunction "1_1") (pintype "unspecified"))
    )
    (net (code "64") (name "unconnected-(SW63-Pad1)") (class "Default")
      (node (ref "SW63") (pin "1") (pinfunction "1_1") (pintype "unspecified"))
    )
    (net (code "65") (name "unconnected-(SW64-Pad1)") (class "Default")
      (node (ref "SW64") (pin "1") (pinfunction "1_1") (pintype "unspecified"))
    )
    (net (code "66") (name "unconnected-(SW65-Pad1)") (class "Default")
      (node (ref "SW65") (pin "1") (pinfunction "1_1") (pintype "unspecified"))
    )
    (net (code "67") (name "unconnected-(SW66-Pad1)") (class "Default")
      (node (ref "SW66") (pin "1") (pinfunction "1_1") (pintype "unspecified"))
    )
    (net (code "68") (name "unconnected-(SW67-Pad1)") (class "Default")
      (node (ref "SW67") (pin "1") (pinfunction "1_1") (pintype "unspecified"))
    )
    (net (code "69") (name "unconnected-(SW68-Pad1)") (class "Default")
      (node (ref "SW68") (pin "1") (pinfunction "1_1") (pintype "unspecified"))
    )
    (net (code "70") (name "unconnected-(SW69-Pad1)") (class "Default")
      (node (ref "SW69") (pin "1") (pinfunction "1_1") (pintype "unspecified"))
    )
    (net (code "71") (name "unconnected-(SW70-Pad1)") (class "Default")
      (node (ref "SW70") (pin "1") (pinfunction "1_1") (pintype "unspecified"))
    )
    (net (code "72") (name "unconnected-(SW71-Pad1)") (class "Default")
      (node (ref "SW71") (pin "1") (pinfunction "1_1") (pintype "unspecified"))
    )
    (net (code "73") (name "unconnected-(SW72-Pad1)") (class "Default")
      (node (ref "SW72") (pin "1") (pinfunction "1_1") (pintype "unspecified"))
    )
    (net (code "74") (name "unconnected-(SW73-Pad1)") (class "Default")
      (node (ref "SW73") (pin "1") (pinfunction "1_1") (pintype "unspecified"))
    )
    (net (code "75") (name "unconnected-(SW74-Pad1)") (class "Default")
      (node (ref "SW74") (pin "1") (pinfunction "1_1") (pintype "unspecified"))
    )
    (net (code "76") (name "unconnected-(SW75-Pad1)") (class "Default")
      (node (ref "SW75") (pin "1") (pinfunction "1_1") (pintype "unspecified"))
    )
    (net (code "77") (name "unconnected-(SW76-Pad1)") (class "Default")
      (node (ref "SW76") (pin "1") (pinfunction "1_1") (pintype "unspecified"))
    )
    (net (code "78") (name "unconnected-(SW78-Pad1)") (class "Default")
      (node (ref "SW78") (pin "1") (pinfunction "1_1") (pintype "unspecified"))
    )
    (net (code "79") (name "unconnected-(SW79-Pad1)") (class "Default")
      (node (ref "SW79") (pin "1") (pinfunction "1_1") (pintype "unspecified"))
    )
    (net (code "80") (name "unconnected-(SW81-Pad1)") (class "Default")
      (node (ref "SW81") (pin "1") (pinfunction "1_1") (pintype "unspecified"))
    )
    (net (code "81") (name "unconnected-(SW82-Pad1)") (class "Default")
      (node (ref "SW82") (pin "1") (pinfunction "1_1") (pintype "unspecified"))
    )
    (net (code "82") (name "unconnected-(SW83-Pad1)") (class "Default")
      (node (ref "SW83") (pin "1") (pinfunction "1_1") (pintype "unspecified"))
    )
    (net (code "83") (name "unconnected-(SW84-Pad1)") (class "Default")
      (node (ref "SW84") (pin "1") (pinfunction "1_1") (pintype "unspecified"))
    )
    (net (code "84") (name "unconnected-(SW85-Pad1)") (class "Default")
      (node (ref "SW85") (pin "1") (pinfunction "1_1") (pintype "unspecified"))
    )
    (net (code "85") (name "unconnected-(SW87-Pad1)") (class "Default")
      (node (ref "SW87") (pin "1") (pinfunction "1_1") (pintype "unspecified"))
    )
    (net (code "86") (name "unconnected-(SW88-Pad1)") (class "Default")
      (node (ref "SW88") (pin "1") (pinfunction "1_1") (pintype "unspecified"))
    )
    (net (code "87") (name "unconnected-(SW89-Pad1)") (class "Default")
      (node (ref "SW89") (pin "1") (pinfunction "1_1") (pintype "unspecified"))
    )
    (net (code "88") (name "unconnected-(SW90-Pad1)") (class "Default")
      (node (ref "SW90") (pin "1") (pinfunction "1_1") (pintype "unspecified"))
    )
    (net (code "89") (name "unconnected-(SW91-Pad1)") (class "Default")
      (node (ref "SW91") (pin "1") (pinfunction "1_1") (pintype "unspecified"))
    )
    (net (code "90") (name "unconnected-(SW92-Pad1)") (class "Default")
      (node (ref "SW92") (pin "1") (pinfunction "1_1") (pintype "unspecified"))
    )
    (net (code "91") (name "unconnected-(SW93-Pad1)") (class "Default")
      (node (ref "SW93") (pin "1") (pinfunction "1_1") (pintype "unspecified"))
    )
    (net (code "92") (name "unconnected-(SW94-Pad1)") (class "Default")
      (node (ref "SW94") (pin "1") (pinfunction "1_1") (pintype "unspecified"))
    )
    (net (code "93") (name "unconnected-(SW96-Pad1)") (class "Default")
      (node (ref "SW96") (pin "1") (pinfunction "1_1") (pintype "unspecified"))
    )
    (net (code "94") (name "unconnected-(SW97-Pad1)") (class "Default")
      (node (ref "SW97") (pin "1") (pinfunction "1_1") (pintype "unspecified"))
    )
    (net (code "95") (name "unconnected-(SW98-Pad1)") (class "Default")
      (node (ref "SW98") (pin "1") (pinfunction "1_1") (pintype "unspecified"))
    )
    (net (code "96") (name "unconnected-(SW99-Pad1)") (class "Default")
      (node (ref "SW99") (pin "1") (pinfunction "1_1") (pintype "unspecified"))
    )
    (net (code "97") (name "unconnected-(SW100-Pad1)") (class "Default")
      (node (ref "SW100") (pin "1") (pinfunction "1_1") (pintype "unspecified"))
    )
    (net (code "98") (name "unconnected-(SW101-Pad1)") (class "Default")
      (node (ref "SW101") (pin "1") (pinfunction "1_1") (pintype "unspecified"))
    )
    (net (code "99") (name "unconnected-(SW102-Pad1)") (class "Default")
      (node (ref "SW102") (pin "1") (pinfunction "1_1") (pintype "unspecified"))
    )
    (net (code "100") (name "unconnected-(SW103-Pad1)") (class "Default")
      (node (ref "SW103") (pin "1") (pinfunction "1_1") (pintype "unspecified"))
    )
    (net (code "101") (name "unconnected-(SW104-Pad1)") (class "Default")
      (node (ref "SW104") (pin "1") (pinfunction "1_1") (pintype "unspecified"))
    )
    (net (code "102") (name "unconnected-(SW105-Pad1)") (class "Default")
      (node (ref "SW105") (pin "1") (pinfunction "1_1") (pintype "unspecified"))
    )
    (net (code "103") (name "unconnected-(SW106-Pad1)") (class "Default")
      (node (ref "SW106") (pin "1") (pinfunction "1_1") (pintype "unspecified"))
    )
    (net (code "104") (name "unconnected-(SW107-Pad1)") (class "Default")
      (node (ref "SW107") (pin "1") (pinfunction "1_1") (pintype "unspecified"))
    )
    (net (code "105") (name "unconnected-(SW108-Pad1)") (class "Default")
      (node (ref "SW108") (pin "1") (pinfunction "1_1") (pintype "unspecified"))
    )
  )
)
